# wifi.net
KiCad netlist of a schematic drawn in Altium Designer
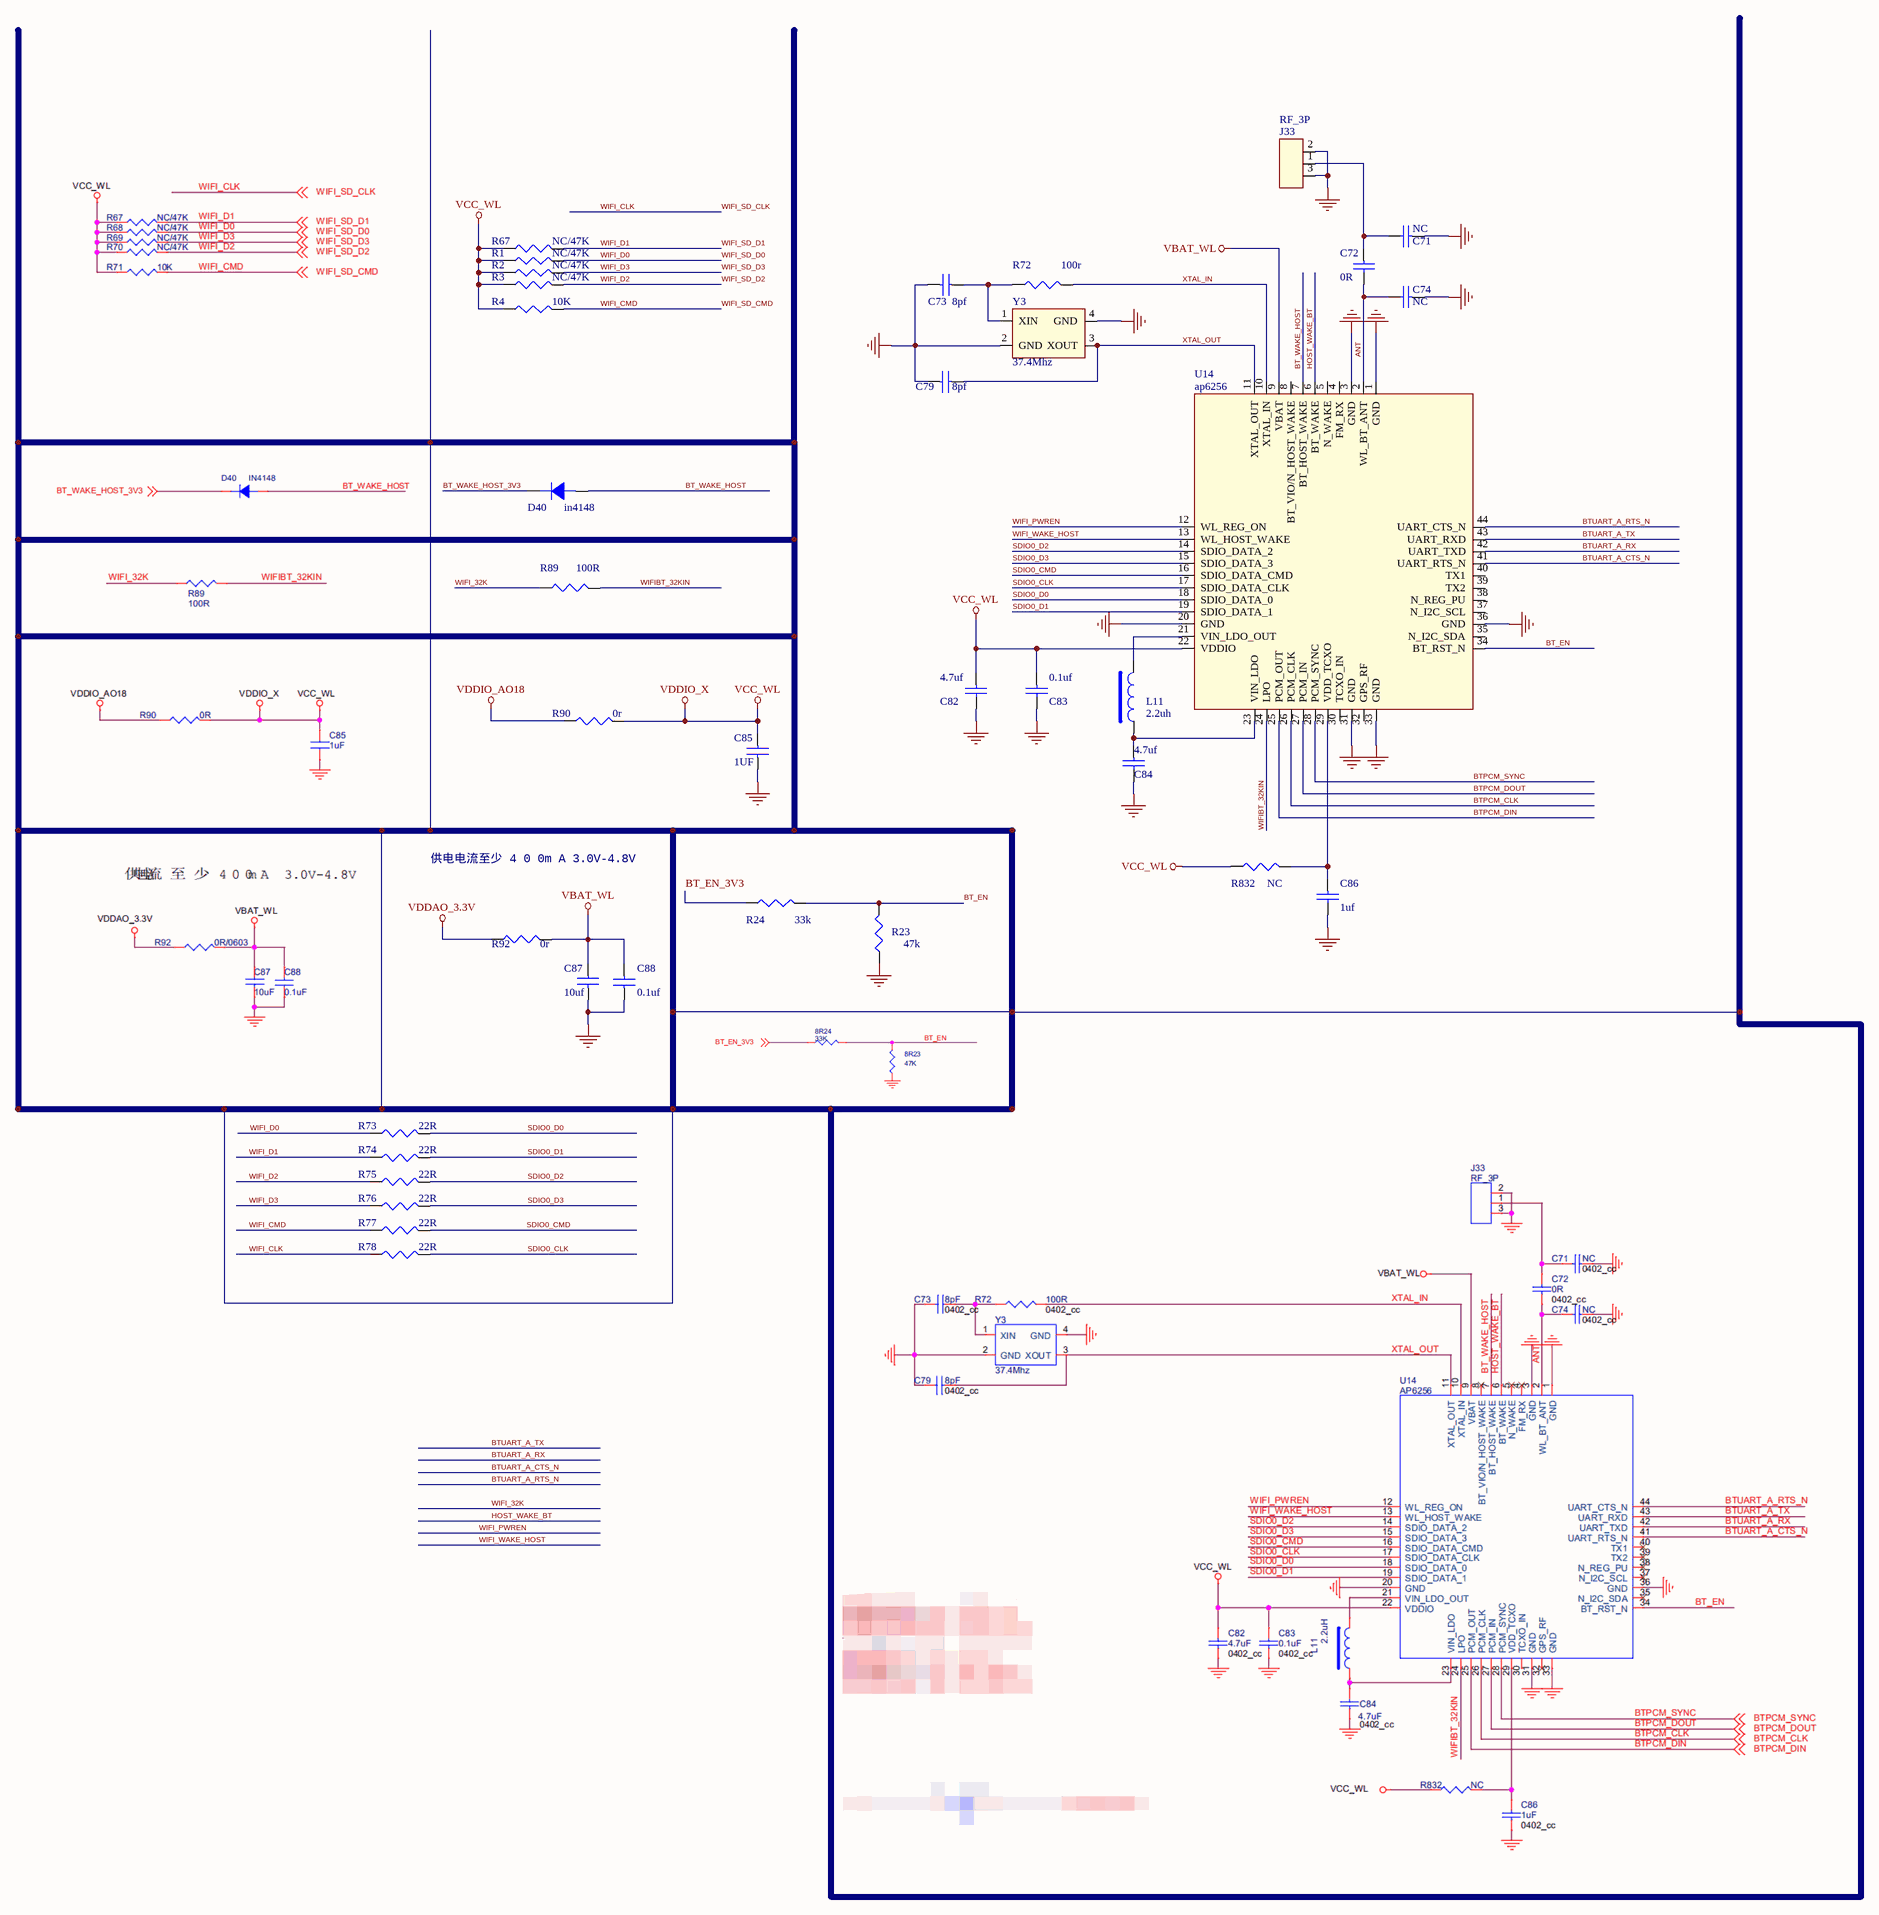
[diagram p0: wifi.SchDoc]

(export (version "E")
  (design (tool "Eeschema 10.0.6"))
  (components
    (comp (ref "C71") (value "NC") (libsource (lib "*") (part "CAPNP_Dup1_1")))
    (comp (ref "C72") (value "0R") (libsource (lib "*") (part "CAPNP_Dup1_1")))
    (comp (ref "C73") (value "8pf") (footprint "C0402") (libsource (lib "*") (part "CAP NP")))
    (comp (ref "C74") (value "NC") (libsource (lib "*") (part "CAPNP_Dup1_1")))
    (comp (ref "C79") (value "8pf") (footprint "C0402") (libsource (lib "*") (part "CAP NP")))
    (comp (ref "C82") (value "4.7uf") (libsource (lib "*") (part "CAPNP_Dup1_1")))
    (comp (ref "C83") (value "0.1uf") (libsource (lib "*") (part "CAPNP_Dup1_1")))
    (comp (ref "C84") (value "4.7uf") (libsource (lib "*") (part "CAPNP_Dup1_1")))
    (comp (ref "C85") (value "1UF") (footprint "C0402") (libsource (lib "*") (part "CAP NP")))
    (comp (ref "C86") (value "1uf") (libsource (lib "*") (part "CAPNP_Dup1_1")))
    (comp (ref "C87") (value "10uf") (footprint "C0402") (libsource (lib "*") (part "CAP NP")))
    (comp (ref "C88") (value "0.1uf") (footprint "C0402") (libsource (lib "*") (part "CAP NP")))
    (comp (ref "D40") (value "in4148") (libsource (lib "*") (part "DIODE")))
    (comp (ref "J33") (value "RF_3P") (libsource (lib "*") (part "CON3_1")))
    (comp (ref "L11") (value "2.2uh") (libsource (lib "*") (part "INDUCTOR_1")))
    (comp (ref "R1") (value "NC/47K") (libsource (lib "*") (part "RESISTOR")))
    (comp (ref "R2") (value "NC/47K") (libsource (lib "*") (part "RESISTOR")))
    (comp (ref "R3") (value "NC/47K") (libsource (lib "*") (part "RESISTOR")))
    (comp (ref "R4") (value "10K") (libsource (lib "*") (part "RESISTOR")))
    (comp (ref "R23") (value "47k") (libsource (lib "*") (part "RESISTOR")))
    (comp (ref "R24") (value "33k") (libsource (lib "*") (part "RESISTOR")))
    (comp (ref "R67") (value "NC/47K") (libsource (lib "*") (part "RESISTOR")))
    (comp (ref "R72") (value "100r") (footprint "R0402") (libsource (lib "*") (part "R_0")))
    (comp (ref "R73") (value "22R") (libsource (lib "*") (part "RESISTOR")))
    (comp (ref "R74") (value "22R") (libsource (lib "*") (part "RESISTOR")))
    (comp (ref "R75") (value "22R") (libsource (lib "*") (part "RESISTOR")))
    (comp (ref "R76") (value "22R") (libsource (lib "*") (part "RESISTOR")))
    (comp (ref "R77") (value "22R") (libsource (lib "*") (part "RESISTOR")))
    (comp (ref "R78") (value "22R") (libsource (lib "*") (part "RESISTOR")))
    (comp (ref "R89") (value "100R") (libsource (lib "*") (part "RESISTOR")))
    (comp (ref "R90") (value "0r") (libsource (lib "*") (part "RESISTOR_1")))
    (comp (ref "R92") (value "0r") (libsource (lib "*") (part "RESISTOR_1")))
    (comp (ref "R832") (value "NC") (libsource (lib "*") (part "RESISTOR")))
    (comp (ref "U14") (value "ap6256") (libsource (lib "*") (part "AP6493_1")))
    (comp (ref "Y3")
      (value "37.4Mhz")
      (footprint "CRY-3225")
      (description "ass")
      (libsource (lib "*") (part "CRYSTAL-4_4"))
    )
  )
  (nets
    (net (code "1") (name "/ANT") (class "Default")
      (node (ref "C72") (pin "1") (pinfunction "1_1") (pintype "passive"))
      (node (ref "C74") (pin "1") (pinfunction "1_1") (pintype "passive"))
      (node (ref "U14") (pin "2") (pinfunction "WL_BT_ANT_2") (pintype "passive"))
    )
    (net (code "2") (name "/BTPCM_CLK") (class "Default")
      (node (ref "U14") (pin "26") (pinfunction "PCM_CLK_26") (pintype "passive"))
    )
    (net (code "3") (name "/BTPCM_DIN") (class "Default")
      (node (ref "U14") (pin "25") (pinfunction "PCM_OUT_25") (pintype "passive"))
    )
    (net (code "4") (name "/BTPCM_DOUT") (class "Default")
      (node (ref "U14") (pin "27") (pinfunction "PCM_IN_27") (pintype "passive"))
    )
    (net (code "5") (name "/BTPCM_SYNC") (class "Default")
      (node (ref "U14") (pin "28") (pinfunction "PCM_SYNC_28") (pintype "passive"))
    )
    (net (code "6") (name "/BTUART_A_CTS_N") (class "Default")
      (node (ref "U14") (pin "41") (pinfunction "UART_RTS_N_41") (pintype "passive"))
    )
    (net (code "7") (name "/BTUART_A_RTS_N") (class "Default")
      (node (ref "U14") (pin "44") (pinfunction "UART_CTS_N_44") (pintype "passive"))
    )
    (net (code "8") (name "/BTUART_A_RX") (class "Default")
      (node (ref "U14") (pin "42") (pinfunction "UART_TXD_42") (pintype "passive"))
    )
    (net (code "9") (name "/BTUART_A_TX") (class "Default")
      (node (ref "U14") (pin "43") (pinfunction "UART_RXD_43") (pintype "passive"))
    )
    (net (code "10") (name "/BT_EN") (class "Default")
      (node (ref "R23") (pin "2") (pinfunction "2_2") (pintype "passive"))
      (node (ref "R24") (pin "2") (pinfunction "2_2") (pintype "passive"))
      (node (ref "U14") (pin "34") (pinfunction "BT_RST_N_34") (pintype "passive"))
    )
    (net (code "11") (name "/BT_EN_3V3") (class "Default")
      (node (ref "R24") (pin "1") (pinfunction "1_1") (pintype "passive"))
    )
    (net (code "12") (name "/BT_WAKE_HOST") (class "Default")
      (node (ref "D40") (pin "1") (pinfunction "A_1") (pintype "passive"))
      (node (ref "U14") (pin "7") (pinfunction "BT_HOST_WAKE_7") (pintype "passive"))
    )
    (net (code "13") (name "/BT_WAKE_HOST_3V3") (class "Default")
      (node (ref "D40") (pin "2") (pinfunction "K_2") (pintype "passive"))
    )
    (net (code "14") (name "/HOST_WAKE_BT") (class "Default")
      (node (ref "U14") (pin "6") (pinfunction "BT_WAKE_6") (pintype "passive"))
    )
    (net (code "15") (name "/SDIO0_CLK") (class "Default")
      (node (ref "R78") (pin "2") (pinfunction "2_2") (pintype "passive"))
      (node (ref "U14") (pin "17") (pinfunction "SDIO_DATA_CLK_17") (pintype "passive"))
    )
    (net (code "16") (name "/SDIO0_CMD") (class "Default")
      (node (ref "R77") (pin "2") (pinfunction "2_2") (pintype "passive"))
      (node (ref "U14") (pin "16") (pinfunction "SDIO_DATA_CMD_16") (pintype "passive"))
    )
    (net (code "17") (name "/SDIO0_D0") (class "Default")
      (node (ref "R73") (pin "2") (pinfunction "2_2") (pintype "passive"))
      (node (ref "U14") (pin "18") (pinfunction "SDIO_DATA_0_18") (pintype "passive"))
    )
    (net (code "18") (name "/SDIO0_D1") (class "Default")
      (node (ref "R74") (pin "2") (pinfunction "2_2") (pintype "passive"))
      (node (ref "U14") (pin "19") (pinfunction "SDIO_DATA_1_19") (pintype "passive"))
    )
    (net (code "19") (name "/SDIO0_D2") (class "Default")
      (node (ref "R75") (pin "2") (pinfunction "2_2") (pintype "passive"))
      (node (ref "U14") (pin "14") (pinfunction "SDIO_DATA_2_14") (pintype "passive"))
    )
    (net (code "20") (name "/SDIO0_D3") (class "Default")
      (node (ref "R76") (pin "2") (pinfunction "2_2") (pintype "passive"))
      (node (ref "U14") (pin "15") (pinfunction "SDIO_DATA_3_15") (pintype "passive"))
    )
    (net (code "21") (name "/WIFIBT_32KIN") (class "Default")
      (node (ref "R89") (pin "1") (pinfunction "1_1") (pintype "passive"))
      (node (ref "U14") (pin "24") (pinfunction "LPO_24") (pintype "passive"))
    )
    (net (code "22") (name "/WIFI_32K") (class "Default")
      (node (ref "R89") (pin "2") (pinfunction "2_2") (pintype "passive"))
    )
    (net (code "23") (name "/WIFI_CLK") (class "Default")
      (node (ref "R78") (pin "1") (pinfunction "1_1") (pintype "passive"))
    )
    (net (code "24") (name "/WIFI_CMD") (class "Default")
      (node (ref "R4") (pin "2") (pinfunction "2_2") (pintype "passive"))
      (node (ref "R77") (pin "1") (pinfunction "1_1") (pintype "passive"))
    )
    (net (code "25") (name "/WIFI_D0") (class "Default")
      (node (ref "R1") (pin "2") (pinfunction "2_2") (pintype "passive"))
      (node (ref "R73") (pin "1") (pinfunction "1_1") (pintype "passive"))
    )
    (net (code "26") (name "/WIFI_D1") (class "Default")
      (node (ref "R67") (pin "2") (pinfunction "2_2") (pintype "passive"))
      (node (ref "R74") (pin "1") (pinfunction "1_1") (pintype "passive"))
    )
    (net (code "27") (name "/WIFI_D2") (class "Default")
      (node (ref "R3") (pin "2") (pinfunction "2_2") (pintype "passive"))
      (node (ref "R75") (pin "1") (pinfunction "1_1") (pintype "passive"))
    )
    (net (code "28") (name "/WIFI_D3") (class "Default")
      (node (ref "R2") (pin "2") (pinfunction "2_2") (pintype "passive"))
      (node (ref "R76") (pin "1") (pinfunction "1_1") (pintype "passive"))
    )
    (net (code "29") (name "/WIFI_PWREN") (class "Default")
      (node (ref "U14") (pin "12") (pinfunction "WL_REG_ON_12") (pintype "passive"))
    )
    (net (code "30") (name "/WIFI_WAKE_HOST") (class "Default")
      (node (ref "U14") (pin "13") (pinfunction "WL_HOST_WAKE_13") (pintype "passive"))
    )
    (net (code "31") (name "/XTAL_IN") (class "Default")
      (node (ref "R72") (pin "2") (pinfunction "2_2") (pintype "passive"))
      (node (ref "U14") (pin "10") (pinfunction "XTAL_IN_10") (pintype "passive"))
    )
    (net (code "32") (name "/XTAL_OUT") (class "Default")
      (node (ref "C79") (pin "2") (pinfunction "2_2") (pintype "passive"))
      (node (ref "U14") (pin "11") (pinfunction "XTAL_OUT_11") (pintype "passive"))
      (node (ref "Y3") (pin "3") (pinfunction "XOUT_3") (pintype "passive"))
    )
    (net (code "33") (name "<NO NET>") (class "Default")
      (node (ref "C71") (pin "2") (pinfunction "2_2") (pintype "passive"))
      (node (ref "C73") (pin "2") (pinfunction "2_2") (pintype "passive"))
      (node (ref "C74") (pin "2") (pinfunction "2_2") (pintype "passive"))
      (node (ref "C79") (pin "1") (pinfunction "1_1") (pintype "passive"))
      (node (ref "C82") (pin "1") (pinfunction "1_1") (pintype "passive"))
      (node (ref "C83") (pin "1") (pinfunction "1_1") (pintype "passive"))
      (node (ref "C84") (pin "1") (pinfunction "1_1") (pintype "passive"))
      (node (ref "C85") (pin "2") (pinfunction "2_2") (pintype "passive"))
      (node (ref "C86") (pin "1") (pinfunction "1_1") (pintype "passive"))
      (node (ref "C87") (pin "2") (pinfunction "2_2") (pintype "passive"))
      (node (ref "C88") (pin "1") (pinfunction "1_1") (pintype "passive"))
      (node (ref "J33") (pin "2") (pinfunction "2_2") (pintype "passive"))
      (node (ref "J33") (pin "3") (pinfunction "3_3") (pintype "passive"))
      (node (ref "R23") (pin "1") (pinfunction "1_1") (pintype "passive"))
      (node (ref "U14") (pin "1") (pinfunction "GND_1") (pintype "power_in"))
      (node (ref "U14") (pin "20") (pinfunction "GND_20") (pintype "power_in"))
      (node (ref "U14") (pin "3") (pinfunction "GND_3") (pintype "power_in"))
      (node (ref "U14") (pin "31") (pinfunction "GND_31") (pintype "power_in"))
      (node (ref "U14") (pin "33") (pinfunction "GND_33") (pintype "power_in"))
      (node (ref "U14") (pin "36") (pinfunction "GND_36") (pintype "power_in"))
      (node (ref "Y3") (pin "2") (pinfunction "GND_2") (pintype "power_in"))
      (node (ref "Y3") (pin "4") (pinfunction "GND_4") (pintype "power_in"))
    )
    (net (code "34") (name "Net-(C71-Pad1)") (class "Default")
      (node (ref "C71") (pin "1") (pinfunction "1_1") (pintype "passive"))
      (node (ref "C72") (pin "2") (pinfunction "2_2") (pintype "passive"))
      (node (ref "J33") (pin "1") (pinfunction "1_1") (pintype "passive"))
    )
    (net (code "35") (name "Net-(U14-VDD_TCXO)") (class "Default")
      (node (ref "C86") (pin "2") (pinfunction "2_2") (pintype "passive"))
      (node (ref "R832") (pin "2") (pinfunction "2_2") (pintype "passive"))
      (node (ref "U14") (pin "29") (pinfunction "VDD_TCXO_29") (pintype "passive"))
    )
    (net (code "36") (name "Net-(U14-VIN_LDO)") (class "Default")
      (node (ref "C84") (pin "2") (pinfunction "2_2") (pintype "passive"))
      (node (ref "L11") (pin "1") (pinfunction "1_1") (pintype "passive"))
      (node (ref "U14") (pin "23") (pinfunction "VIN_LDO_23") (pintype "passive"))
    )
    (net (code "37") (name "Net-(U14-VIN_LDO_OUT)") (class "Default")
      (node (ref "L11") (pin "2") (pinfunction "2_2") (pintype "passive"))
      (node (ref "U14") (pin "21") (pinfunction "VIN_LDO_OUT_21") (pintype "passive"))
    )
    (net (code "38") (name "Net-(Y3-XIN)") (class "Default")
      (node (ref "C73") (pin "1") (pinfunction "1_1") (pintype "passive"))
      (node (ref "R72") (pin "1") (pinfunction "1_1") (pintype "passive"))
      (node (ref "Y3") (pin "1") (pinfunction "XIN_1") (pintype "passive"))
    )
    (net (code "39") (name "VBAT_WL") (class "Default")
      (node (ref "C87") (pin "1") (pinfunction "1_1") (pintype "passive"))
      (node (ref "C88") (pin "2") (pinfunction "2_2") (pintype "passive"))
      (node (ref "R92") (pin "1") (pinfunction "1_1") (pintype "passive"))
      (node (ref "U14") (pin "9") (pinfunction "VBAT_9") (pintype "passive"))
    )
    (net (code "40") (name "VCC_WL") (class "Default")
      (node (ref "C82") (pin "2") (pinfunction "2_2") (pintype "passive"))
      (node (ref "C83") (pin "2") (pinfunction "2_2") (pintype "passive"))
      (node (ref "C85") (pin "1") (pinfunction "1_1") (pintype "passive"))
      (node (ref "R1") (pin "1") (pinfunction "1_1") (pintype "passive"))
      (node (ref "R2") (pin "1") (pinfunction "1_1") (pintype "passive"))
      (node (ref "R3") (pin "1") (pinfunction "1_1") (pintype "passive"))
      (node (ref "R4") (pin "1") (pinfunction "1_1") (pintype "passive"))
      (node (ref "R67") (pin "1") (pinfunction "1_1") (pintype "passive"))
      (node (ref "R832") (pin "1") (pinfunction "1_1") (pintype "passive"))
      (node (ref "R90") (pin "1") (pinfunction "1_1") (pintype "passive"))
      (node (ref "U14") (pin "22") (pinfunction "VDDIO_22") (pintype "passive"))
    )
    (net (code "41") (name "VDDAO_3.3V") (class "Default")
      (node (ref "R92") (pin "2") (pinfunction "2_2") (pintype "passive"))
    )
    (net (code "42") (name "VDDIO_AO18") (class "Default")
      (node (ref "R90") (pin "2") (pinfunction "2_2") (pintype "passive"))
    )
    (net (code "43") (name "unconnected-(U14-BT_VIO{slash}N_HOST_WAKE-Pad8)") (class "Default")
      (node (ref "U14") (pin "8") (pinfunction "BT_VIO/N_HOST_WAKE_8") (pintype "passive"))
    )
    (net (code "44") (name "unconnected-(U14-FM_RX-Pad4)") (class "Default")
      (node (ref "U14") (pin "4") (pinfunction "FM_RX_4") (pintype "passive"))
    )
    (net (code "45") (name "unconnected-(U14-GPS_RF-Pad32)") (class "Default")
      (node (ref "U14") (pin "32") (pinfunction "GPS_RF_32") (pintype "passive"))
    )
    (net (code "46") (name "unconnected-(U14-N_I2C_SCL-Pad37)") (class "Default")
      (node (ref "U14") (pin "37") (pinfunction "N_I2C_SCL_37") (pintype "passive"))
    )
    (net (code "47") (name "unconnected-(U14-N_I2C_SDA-Pad35)") (class "Default")
      (node (ref "U14") (pin "35") (pinfunction "N_I2C_SDA_35") (pintype "passive"))
    )
    (net (code "48") (name "unconnected-(U14-N_REG_PU-Pad38)") (class "Default")
      (node (ref "U14") (pin "38") (pinfunction "N_REG_PU_38") (pintype "passive"))
    )
    (net (code "49") (name "unconnected-(U14-N_WAKE-Pad5)") (class "Default")
      (node (ref "U14") (pin "5") (pinfunction "N_WAKE_5") (pintype "passive"))
    )
    (net (code "50") (name "unconnected-(U14-TCXO_IN-Pad30)") (class "Default")
      (node (ref "U14") (pin "30") (pinfunction "TCXO_IN_30") (pintype "passive"))
    )
    (net (code "51") (name "unconnected-(U14-TX1-Pad40)") (class "Default")
      (node (ref "U14") (pin "40") (pinfunction "TX1_40") (pintype "passive"))
    )
    (net (code "52") (name "unconnected-(U14-TX2-Pad39)") (class "Default")
      (node (ref "U14") (pin "39") (pinfunction "TX2_39") (pintype "passive"))
    )
  )
)
